# Trottinette_Telemetrie_Connectors.net
KiCad netlist of a schematic drawn in Altium Designer
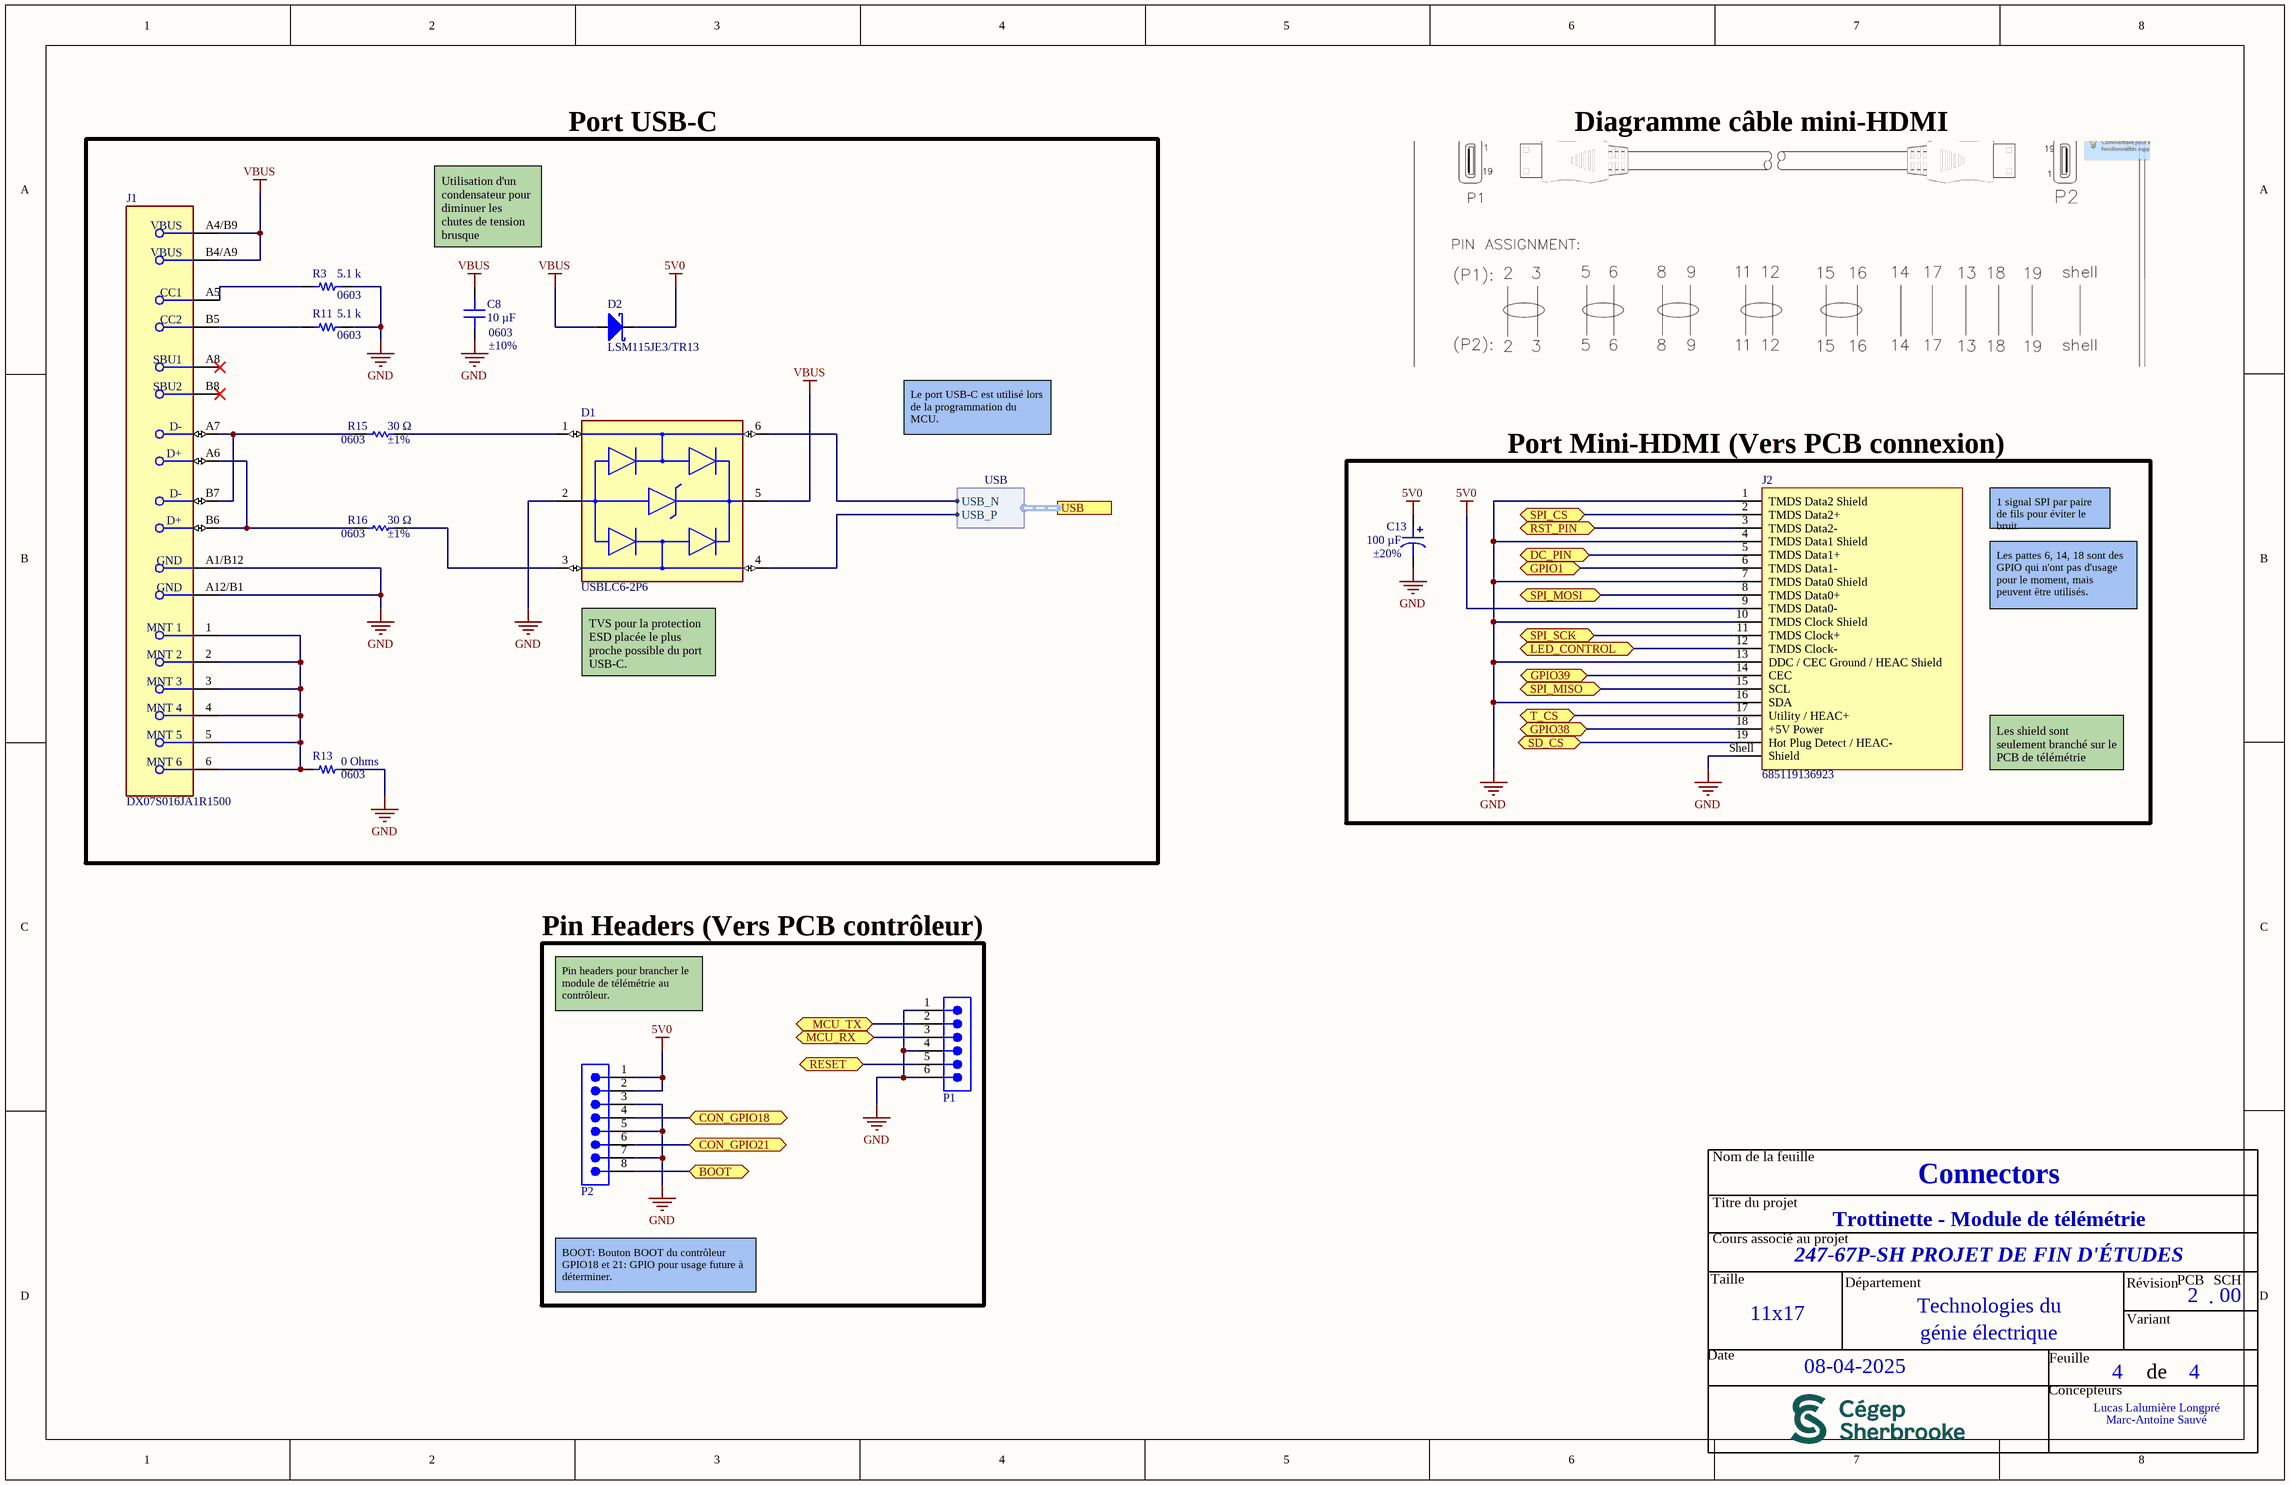
[diagram p0: Trottinette_Telemetrie_Connectors.SchDoc]

(export (version "E")
  (design (tool "Eeschema 10.0.6"))
  (components
    (comp (ref "C8")
      (value "10 µF")
      (footprint "CAP 0603_1608")
      (description "CAP CER 10UF 10V X5R 0603")
      (fields
        (field (name "PART NUMBER") "GRT188R61A106KE13D")
        (field (name "DEVICE PACKAGE") "0603")
        (field (name "MANUFACTURER") "Murata Electronics")
        (field (name "TOLERANCE") "±10%")
      )
      (libsource (lib "Celestial Altium Library - altium_library") (part "Capacitor"))
    )
    (comp (ref "C13")
      (value "100 µF")
      (footprint "CAP ALSMD 6.6MM H6.1MM")
      (description "CAP ALUM 100UF 20% 10V SMD")
      (fields
        (field (name "PART NUMBER") "10SGV100M6.3X6.1")
        (field (name "MANUFACTURER") "Rubycon")
        (field (name "TOLERANCE") "±20%")
      )
      (libsource (lib "Celestial Altium Library - altium_library") (part "Polarised Capacitor"))
    )
    (comp (ref "D1")
      (value "USBLC6-2P6")
      (footprint "FP-SOT-666-MFG")
      (description "TVS DIODE 5.25V 17V SOT666")
      (libsource (lib "Altium Content Vault") (part "c871e55f7e3243d341edbd671b98d92"))
    )
    (comp (ref "D2")
      (value "LSM115JE3/TR13")
      (footprint "DIOM4336X33N")
      (description "DIODE SCHOTTKY 15V 1A DO214BA")
      (libsource (lib "Cegep de Sherbrooke") (part "LSM115JE3/TR13"))
    )
    (comp (ref "J1")
      (value "DX07S016JA1R1500")
      (footprint "FP-DX07S016JA1R1500-MFG")
      (description "CONN RCP USB2.0 TYP C 24P SMD RA")
      (libsource (lib "Altium Content Vault") (part "7f3e9989102a0f22bff9cb010881d34"))
    )
    (comp (ref "J2")
      (value "685119136923")
      (footprint "685119136923")
      (libsource (lib "Altium Content Vault") (part "HDMI_Type C"))
    )
    (comp (ref "P1")
      (value "61300611121")
      (footprint "61300611121")
      (description "WR-PHD Pin Header, THT, Vertical, pitch 2.54mm, 1 Row, 6P")
      (fields (field (name "MANUFACTURER") "Wurth Elektronik"))
      (libsource (lib "Altium_WR-PHD_rev24a") (part "61300611121"))
    )
    (comp (ref "P2")
      (value "61300811121")
      (footprint "61300811121")
      (description "WR-PHD Pin Header, THT, Vertical, pitch 2.54mm, 1 Row, 8P")
      (fields (field (name "MANUFACTURER") "Wurth Elektronik"))
      (libsource (lib "Altium_WR-PHD_rev24a") (part "61300811121"))
    )
    (comp (ref "R3")
      (value "5.1 k")
      (footprint "RES 0603_1608")
      (description "RES 5.1K OHM 1% 1/10W 0603")
      (fields
        (field (name "PART NUMBER") "RMCF0603FT5K10")
        (field (name "MANUFACTURER") "Stackpole Electronics Inc")
        (field (name "PACKAGE / CASE") "0603")
      )
      (libsource (lib "Celestial Altium Library - altium_library") (part "Resistor"))
    )
    (comp (ref "R11")
      (value "5.1 k")
      (footprint "RES 0603_1608")
      (description "RES 5.1K OHM 1% 1/10W 0603")
      (fields
        (field (name "PART NUMBER") "RMCF0603FT5K10")
        (field (name "MANUFACTURER") "Stackpole Electronics Inc")
        (field (name "PACKAGE / CASE") "0603")
      )
      (libsource (lib "Celestial Altium Library - altium_library") (part "Resistor"))
    )
    (comp (ref "R13")
      (value "0 Ohms")
      (footprint "RES 0603_1608")
      (description "0603 26 AMP JUMPER")
      (fields
        (field (name "PART NUMBER") "JR0603X26E")
        (field (name "MANUFACTURER") "Ohmite")
        (field (name "SUPPLIER DEVICE PACKAGE") "0603")
      )
      (libsource (lib "Celestial Altium Library - altium_library") (part "Resistor"))
    )
    (comp (ref "R15")
      (value "ERJ3EKF30R0V")
      (footprint "RESC1608X55X30LL15T15")
      (fields (field (name "MANUFACTURER") "Panasonic"))
      (libsource (lib "Altium Content Vault") (part "RES"))
    )
    (comp (ref "R16")
      (value "ERJ3EKF30R0V")
      (footprint "RESC1608X55X30LL15T15")
      (fields (field (name "MANUFACTURER") "Panasonic"))
      (libsource (lib "Altium Content Vault") (part "RES"))
    )
  )
  (nets
    (net (code "2") (name "/BOOT") (class "Default")
      (node (ref "P2") (pin "8") (pinfunction "8_8") (pintype "passive"))
    )
    (net (code "3") (name "/CON_GPIO18") (class "Default")
      (node (ref "P2") (pin "4") (pinfunction "4_4") (pintype "passive"))
    )
    (net (code "4") (name "/CON_GPIO21") (class "Default")
      (node (ref "P2") (pin "6") (pinfunction "6_6") (pintype "passive"))
    )
    (net (code "5") (name "/DC_PIN") (class "Default")
      (node (ref "J2") (pin "5") (pinfunction "TMDS_Data1+_5") (pintype "passive"))
    )
    (net (code "6") (name "/GPIO1") (class "Default")
      (node (ref "J2") (pin "6") (pinfunction "TMDS_Data1-_6") (pintype "passive"))
    )
    (net (code "7") (name "/GPIO38") (class "Default")
      (node (ref "J2") (pin "18") (pinfunction "+5V_Power_18") (pintype "passive"))
    )
    (net (code "8") (name "/GPIO39") (class "Default")
      (node (ref "J2") (pin "14") (pinfunction "CEC_14") (pintype "passive"))
    )
    (net (code "9") (name "/LED_CONTROL") (class "Default")
      (node (ref "J2") (pin "12") (pinfunction "TMDS_Clock-_12") (pintype "passive"))
    )
    (net (code "10") (name "/MCU_RX") (class "Default")
      (node (ref "P1") (pin "3") (pinfunction "3_3") (pintype "passive"))
    )
    (net (code "11") (name "/MCU_TX") (class "Default")
      (node (ref "P1") (pin "2") (pinfunction "2_2") (pintype "passive"))
    )
    (net (code "12") (name "/RESET") (class "Default")
      (node (ref "P1") (pin "5") (pinfunction "5_5") (pintype "passive"))
    )
    (net (code "13") (name "/RST_PIN") (class "Default")
      (node (ref "J2") (pin "3") (pinfunction "TMDS_Data2-_3") (pintype "passive"))
    )
    (net (code "14") (name "/SD_CS") (class "Default")
      (node (ref "J2") (pin "19") (pinfunction "Hot_Plug_Detect_/_HEAC-_19") (pintype "passive"))
    )
    (net (code "15") (name "/SPI_CS") (class "Default")
      (node (ref "J2") (pin "2") (pinfunction "TMDS_Data2+_2") (pintype "passive"))
    )
    (net (code "16") (name "/SPI_MISO") (class "Default")
      (node (ref "J2") (pin "15") (pinfunction "SCL_15") (pintype "passive"))
    )
    (net (code "17") (name "/SPI_MOSI") (class "Default")
      (node (ref "J2") (pin "8") (pinfunction "TMDS_Data0+_8") (pintype "passive"))
    )
    (net (code "18") (name "/SPI_SCK") (class "Default")
      (node (ref "J2") (pin "11") (pinfunction "TMDS_Clock+_11") (pintype "passive"))
    )
    (net (code "19") (name "/T_CS") (class "Default")
      (node (ref "J2") (pin "17") (pinfunction "Utility_/_HEAC+_17") (pintype "passive"))
    )
    (net (code "20") (name "/USB_N") (class "Default")
      (node (ref "D1") (pin "6") (pinfunction "I/O1_6") (pintype "bidirectional"))
    )
    (net (code "21") (name "/USB_P") (class "Default")
      (node (ref "D1") (pin "4") (pinfunction "I/O2_4") (pintype "bidirectional"))
    )
    (net (code "23") (name "5V0") (class "Default")
      (node (ref "C13") (pin "1") (pinfunction "1_1") (pintype "passive"))
      (node (ref "D2") (pin "1") (pinfunction "K_1") (pintype "passive"))
      (node (ref "J2") (pin "9") (pinfunction "TMDS_Data0-_9") (pintype "passive"))
      (node (ref "P2") (pin "1") (pinfunction "1_1") (pintype "passive"))
      (node (ref "P2") (pin "2") (pinfunction "2_2") (pintype "passive"))
    )
    (net (code "24") (name "GND") (class "Default")
      (node (ref "C13") (pin "2") (pinfunction "2_2") (pintype "passive"))
      (node (ref "C8") (pin "1") (pinfunction "1_1") (pintype "passive"))
      (node (ref "D1") (pin "2") (pinfunction "GND_2") (pintype "power_in"))
      (node (ref "J1") (pin "A1/B12") (pinfunction "GND_A1/B12") (pintype "power_in"))
      (node (ref "J1") (pin "A12/B1") (pinfunction "GND_A12/B1") (pintype "power_in"))
      (node (ref "J2") (pin "1") (pinfunction "TMDS_Data2_Shield_1") (pintype "passive"))
      (node (ref "J2") (pin "10") (pinfunction "TMDS_Clock_Shield_10") (pintype "passive"))
      (node (ref "J2") (pin "13") (pinfunction "DDC_/_CEC_Ground_/_HEAC_Shield_13") (pintype "passive"))
      (node (ref "J2") (pin "16") (pinfunction "SDA_16") (pintype "passive"))
      (node (ref "J2") (pin "4") (pinfunction "TMDS_Data1_Shield_4") (pintype "passive"))
      (node (ref "J2") (pin "7") (pinfunction "TMDS_Data0_Shield_7") (pintype "passive"))
      (node (ref "J2") (pin "Shell") (pinfunction "Shield_Shell") (pintype "passive"))
      (node (ref "P1") (pin "1") (pinfunction "1_1") (pintype "passive"))
      (node (ref "P1") (pin "4") (pinfunction "4_4") (pintype "passive"))
      (node (ref "P1") (pin "6") (pinfunction "6_6") (pintype "passive"))
      (node (ref "P2") (pin "3") (pinfunction "3_3") (pintype "passive"))
      (node (ref "P2") (pin "5") (pinfunction "5_5") (pintype "passive"))
      (node (ref "P2") (pin "7") (pinfunction "7_7") (pintype "passive"))
      (node (ref "R11") (pin "1") (pinfunction "1_1") (pintype "passive"))
      (node (ref "R13") (pin "2") (pinfunction "2_2") (pintype "passive"))
      (node (ref "R3") (pin "1") (pinfunction "1_1") (pintype "passive"))
    )
    (net (code "25") (name "Net-(D1-I{slash}O1-Pad1)") (class "Default")
      (node (ref "D1") (pin "1") (pinfunction "I/O1_1") (pintype "bidirectional"))
      (node (ref "R15") (pin "2") (pinfunction "2_2") (pintype "passive"))
    )
    (net (code "26") (name "Net-(D1-I{slash}O2-Pad3)") (class "Default")
      (node (ref "D1") (pin "3") (pinfunction "I/O2_3") (pintype "bidirectional"))
      (node (ref "R16") (pin "2") (pinfunction "2_2") (pintype "passive"))
    )
    (net (code "27") (name "Net-(J1-CC1)") (class "Default")
      (node (ref "J1") (pin "A5") (pinfunction "CC1_A5") (pintype "passive"))
      (node (ref "R3") (pin "2") (pinfunction "2_2") (pintype "passive"))
    )
    (net (code "28") (name "Net-(J1-CC2)") (class "Default")
      (node (ref "J1") (pin "B5") (pinfunction "CC2_B5") (pintype "passive"))
      (node (ref "R11") (pin "2") (pinfunction "2_2") (pintype "passive"))
    )
    (net (code "29") (name "Net-(J1-D+-PadA6)") (class "Default")
      (node (ref "J1") (pin "A6") (pinfunction "D+_A6") (pintype "bidirectional"))
      (node (ref "J1") (pin "B6") (pinfunction "D+_B6") (pintype "bidirectional"))
      (node (ref "R16") (pin "1") (pinfunction "1_1") (pintype "passive"))
    )
    (net (code "30") (name "Net-(J1-D--PadA7)") (class "Default")
      (node (ref "J1") (pin "A7") (pinfunction "D-_A7") (pintype "bidirectional"))
      (node (ref "J1") (pin "B7") (pinfunction "D-_B7") (pintype "bidirectional"))
      (node (ref "R15") (pin "1") (pinfunction "1_1") (pintype "passive"))
    )
    (net (code "31") (name "Net-(J1-MNT_1)") (class "Default")
      (node (ref "J1") (pin "1") (pinfunction "MNT_1_1") (pintype "passive"))
      (node (ref "J1") (pin "2") (pinfunction "MNT_2_2") (pintype "passive"))
      (node (ref "J1") (pin "3") (pinfunction "MNT_3_3") (pintype "passive"))
      (node (ref "J1") (pin "4") (pinfunction "MNT_4_4") (pintype "passive"))
      (node (ref "J1") (pin "5") (pinfunction "MNT_5_5") (pintype "passive"))
      (node (ref "J1") (pin "6") (pinfunction "MNT_6_6") (pintype "passive"))
      (node (ref "R13") (pin "1") (pinfunction "1_1") (pintype "passive"))
    )
    (net (code "32") (name "VBUS") (class "Default")
      (node (ref "C8") (pin "2") (pinfunction "2_2") (pintype "passive"))
      (node (ref "D1") (pin "5") (pinfunction "VBUS_5") (pintype "power_in"))
      (node (ref "D2") (pin "2") (pinfunction "A_2") (pintype "passive"))
      (node (ref "J1") (pin "A4/B9") (pinfunction "VBUS_A4/B9") (pintype "power_in"))
      (node (ref "J1") (pin "B4/A9") (pinfunction "VBUS_B4/A9") (pintype "power_in"))
    )
    (net (code "33") (name "unconnected-(J1-SBU1-PadA8)") (class "Default")
      (node (ref "J1") (pin "A8") (pinfunction "SBU1_A8") (pintype "passive+no_connect"))
    )
    (net (code "34") (name "unconnected-(J1-SBU2-PadB8)") (class "Default")
      (node (ref "J1") (pin "B8") (pinfunction "SBU2_B8") (pintype "passive+no_connect"))
    )
  )
)
